# bappr_easyeda_file_source.net
KiCad netlist of a schematic drawn in EasyEDA
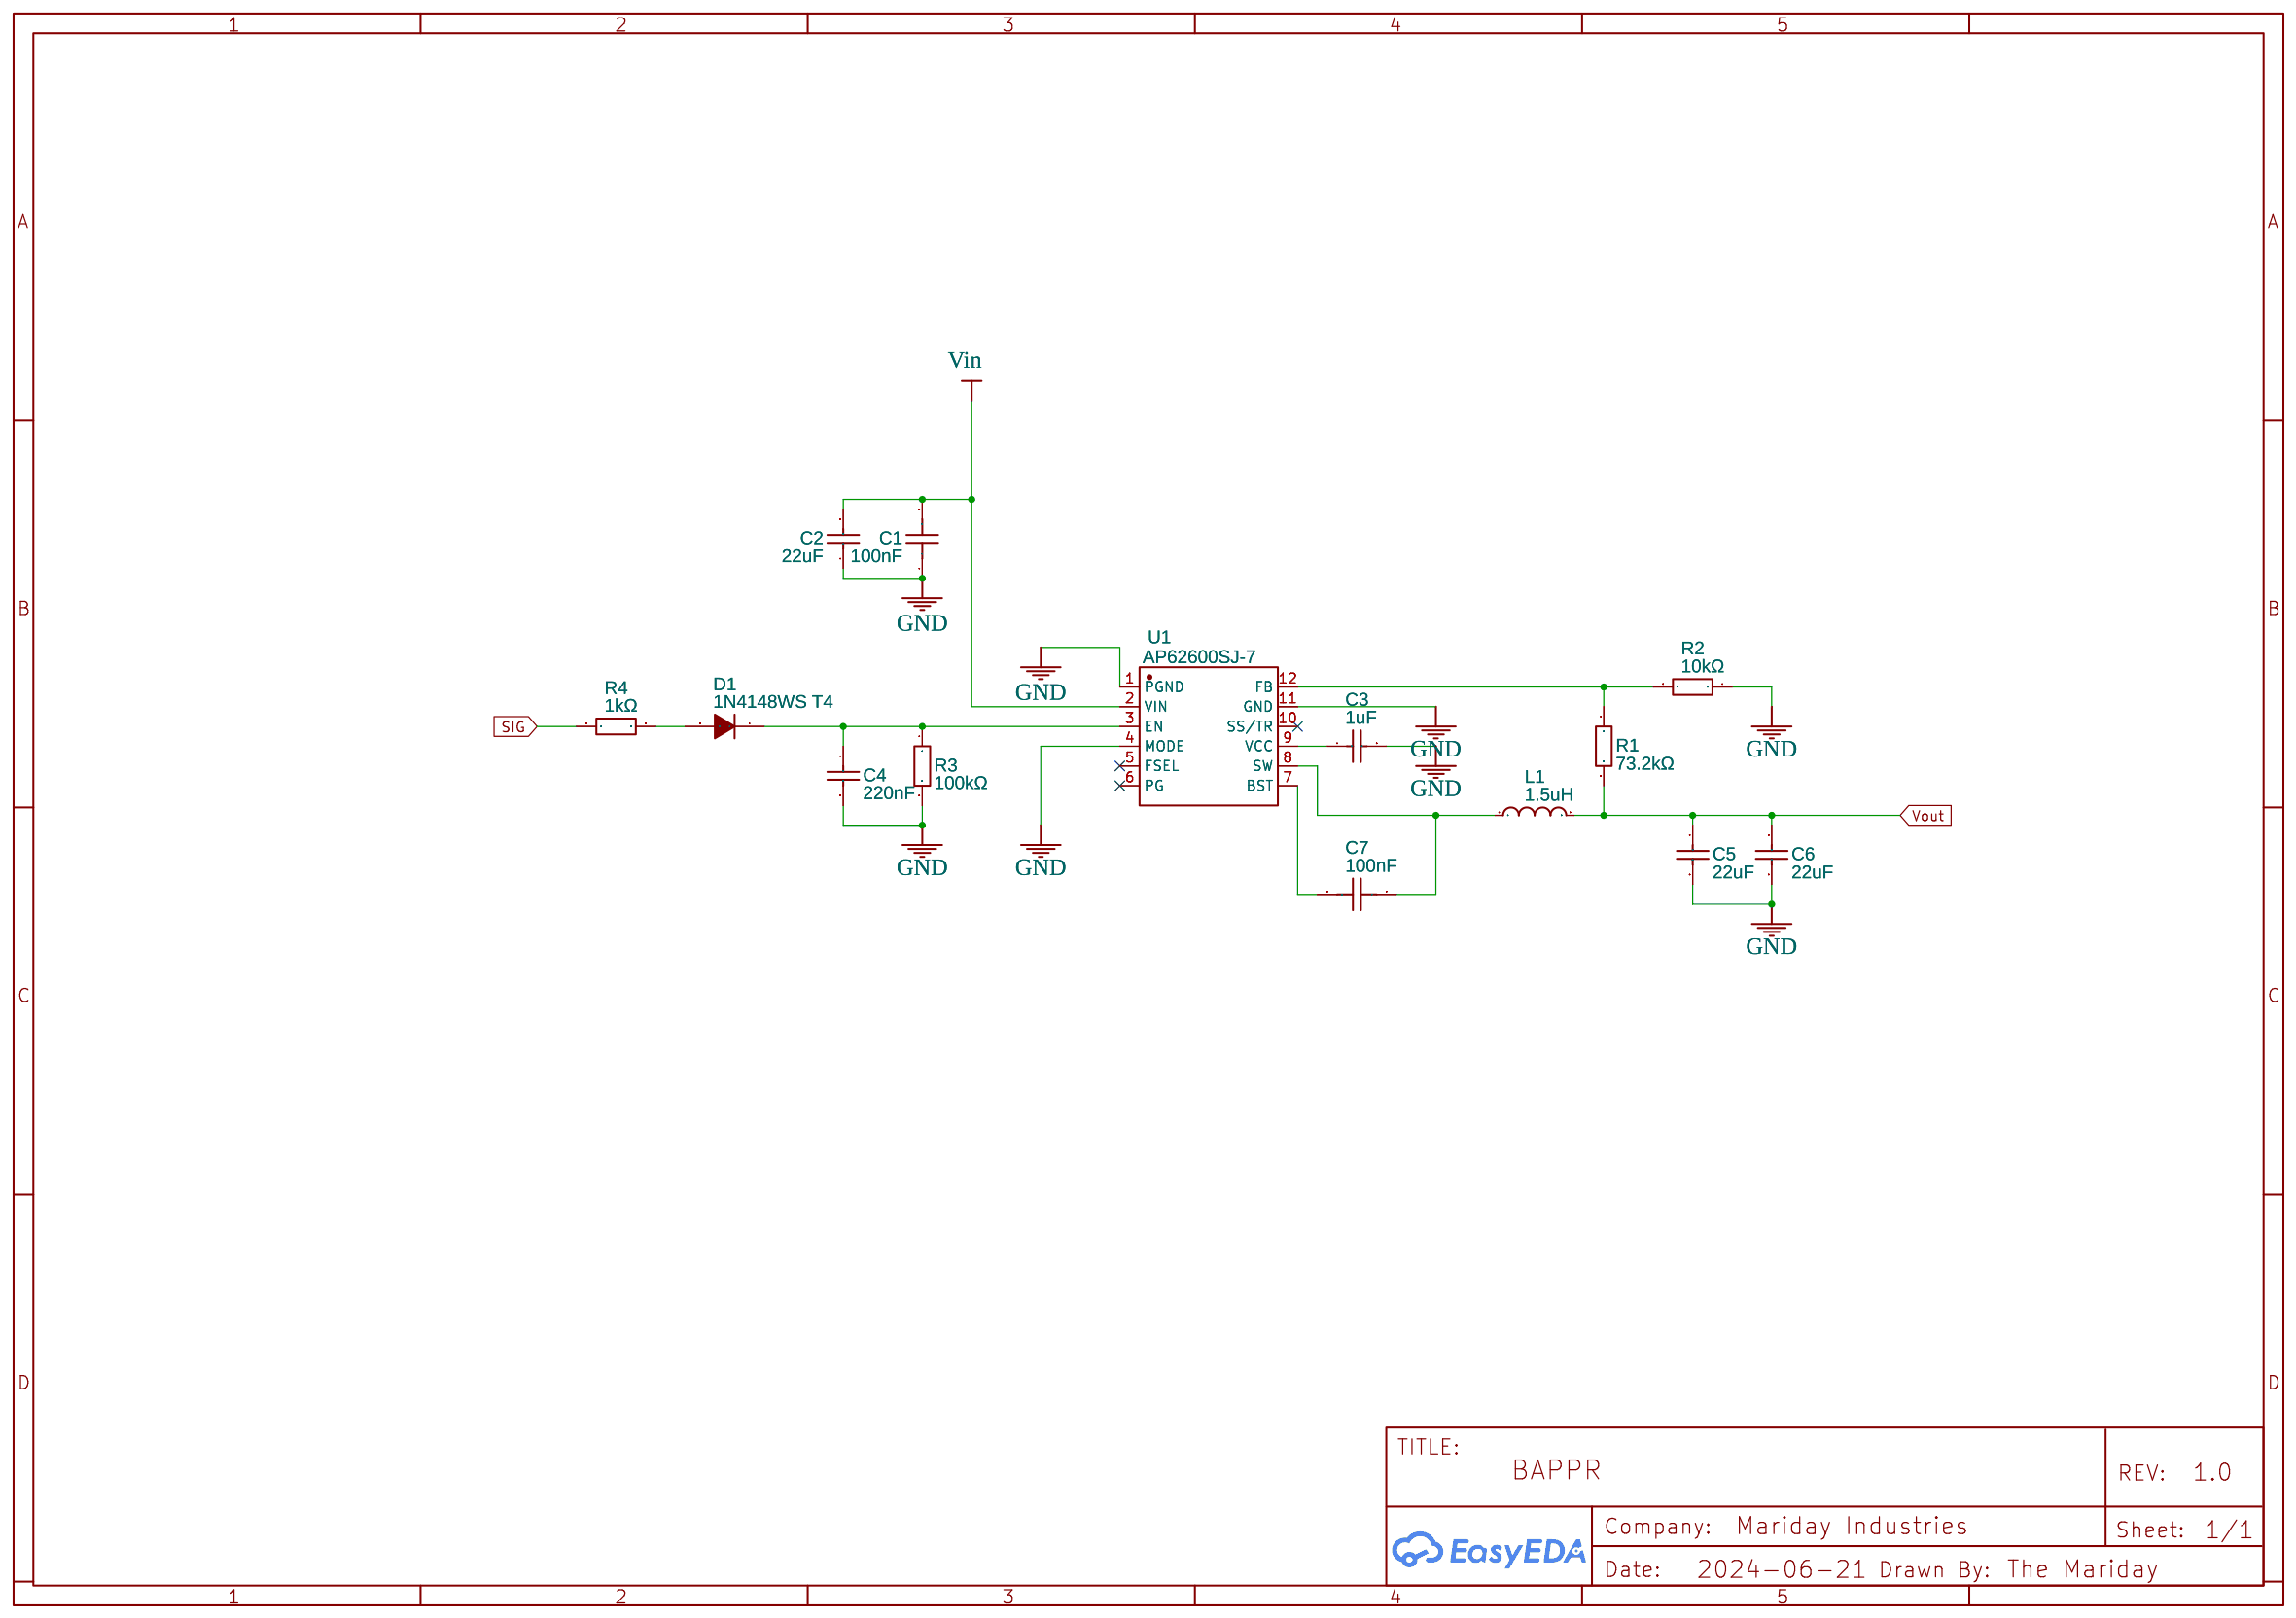
[diagram p0: schematic sheet]

(export (version "E")
  (design (tool "Eeschema 10.0.6"))
  (components
    (comp (ref "C1")
      (value "100nF")
      (fields
        (field (name "Manufacturer Part") "CC0603KRX7R9BB104")
        (field (name "Manufacturer") "YAGEO(国巨)")
      )
      (libsource (lib "") (part "CC0603KRX7R9BB104"))
    )
    (comp (ref "C2")
      (value "22uF")
      (fields
        (field (name "Manufacturer Part") "CL31A226KAHNNNE")
        (field (name "Manufacturer") "SAMSUNG(三星)")
      )
      (libsource (lib "") (part "CL31A226KAHNNNE_1"))
    )
    (comp (ref "C3")
      (value "1uF")
      (fields
        (field (name "Manufacturer Part") "CL10A105KB8NNNC")
        (field (name "Manufacturer") "SAMSUNG(三星)")
      )
      (libsource (lib "") (part "CL10A105KB8NNNC"))
    )
    (comp (ref "C4")
      (value "220nF")
      (fields
        (field (name "Manufacturer Part") "CL10B224KA8NNNC")
        (field (name "Manufacturer") "SAMSUNG(三星)")
      )
      (libsource (lib "") (part "CL10B224KA8NNNC"))
    )
    (comp (ref "C5")
      (value "22uF")
      (fields
        (field (name "Manufacturer Part") "CL31A226KAHNNNE")
        (field (name "Manufacturer") "SAMSUNG(三星)")
      )
      (libsource (lib "") (part "CL31A226KAHNNNE"))
    )
    (comp (ref "C6")
      (value "22uF")
      (fields
        (field (name "Manufacturer Part") "CL31A226KAHNNNE")
        (field (name "Manufacturer") "SAMSUNG(三星)")
      )
      (libsource (lib "") (part "CL31A226KAHNNNE"))
    )
    (comp (ref "C7")
      (value "100nF")
      (fields
        (field (name "Manufacturer Part") "CC0603KRX7R9BB104")
        (field (name "Manufacturer") "YAGEO(国巨)")
      )
      (libsource (lib "") (part "CC0603KRX7R9BB104_1"))
    )
    (comp (ref "D1")
      (value "1N4148WS T4")
      (fields (field (name "Manufacturer Part") "1N4148WS") (field (name "Manufacturer") "CJ(江苏长电/长晶)"))
      (libsource (lib "") (part "1N4148WS T4"))
    )
    (comp (ref "L1")
      (value "1.5uH")
      (fields
        (field (name "Manufacturer Part") "IHLP2525CZER1R5M01")
        (field (name "Manufacturer") "VISHAY(威世)")
      )
      (libsource (lib "") (part "IHLP2525CZER1R5M01"))
    )
    (comp (ref "R1")
      (value "73.2kΩ")
      (fields
        (field (name "Manufacturer Part") "0603WAF7322T5E")
        (field (name "Manufacturer") "UNI-ROYAL(厚声)")
      )
      (libsource (lib "") (part "0603WAF7322T5E"))
    )
    (comp (ref "R2")
      (value "10kΩ")
      (fields
        (field (name "Manufacturer Part") "0603WAF1002T5E")
        (field (name "Manufacturer") "UNI-ROYAL(厚声)")
      )
      (libsource (lib "") (part "0603WAF1002T5E"))
    )
    (comp (ref "R3")
      (value "100kΩ")
      (fields
        (field (name "Manufacturer Part") "0603WAF1003T5E")
        (field (name "Manufacturer") "UNI-ROYAL(厚声)")
      )
      (libsource (lib "") (part "0603WAF1003T5E"))
    )
    (comp (ref "R4")
      (value "1kΩ")
      (fields
        (field (name "Manufacturer Part") "0603WAF1001T5E")
        (field (name "Manufacturer") "UNI-ROYAL(厚声)")
      )
      (libsource (lib "") (part "0603WAF1001T5E"))
    )
    (comp (ref "U1")
      (value "AP62600SJ-7")
      (fields (field (name "Manufacturer") "DIODES(美台)"))
      (libsource (lib "") (part "AP62600SJ-7"))
    )
  )
  (nets
    (net (code "1") (name "GND") (class "Default")
      (node (ref "C1") (pin "1") (pinfunction "1_1") (pintype "unspecified"))
      (node (ref "C2") (pin "1") (pinfunction "1_1") (pintype "input"))
      (node (ref "C3") (pin "2") (pinfunction "2_2") (pintype "input"))
      (node (ref "C4") (pin "2") (pinfunction "2_2") (pintype "input"))
      (node (ref "C5") (pin "2") (pinfunction "2_2") (pintype "input"))
      (node (ref "C6") (pin "2") (pinfunction "2_2") (pintype "input"))
      (node (ref "R2") (pin "1") (pinfunction "1_1") (pintype "input"))
      (node (ref "R3") (pin "2") (pinfunction "2_2") (pintype "input"))
      (node (ref "U1") (pin "1") (pinfunction "PGND_1") (pintype "unspecified"))
      (node (ref "U1") (pin "11") (pinfunction "GND_11") (pintype "unspecified"))
      (node (ref "U1") (pin "4") (pinfunction "MODE_4") (pintype "unspecified"))
    )
    (net (code "2") (name "Net-(D1-A)") (class "Default")
      (node (ref "D1") (pin "2") (pinfunction "A_2") (pintype "unspecified"))
      (node (ref "R4") (pin "2") (pinfunction "2_2") (pintype "input"))
    )
    (net (code "3") (name "Net-(D1-K)") (class "Default")
      (node (ref "C4") (pin "1") (pinfunction "1_1") (pintype "input"))
      (node (ref "D1") (pin "1") (pinfunction "K_1") (pintype "unspecified"))
      (node (ref "R3") (pin "1") (pinfunction "1_1") (pintype "input"))
      (node (ref "U1") (pin "3") (pinfunction "EN_3") (pintype "unspecified"))
    )
    (net (code "4") (name "Net-(U1-BST)") (class "Default")
      (node (ref "C7") (pin "2") (pinfunction "2_2") (pintype "unspecified"))
      (node (ref "U1") (pin "7") (pinfunction "BST_7") (pintype "unspecified"))
    )
    (net (code "5") (name "Net-(U1-FB)") (class "Default")
      (node (ref "R1") (pin "1") (pinfunction "1_1") (pintype "input"))
      (node (ref "R2") (pin "2") (pinfunction "2_2") (pintype "input"))
      (node (ref "U1") (pin "12") (pinfunction "FB_12") (pintype "unspecified"))
    )
    (net (code "6") (name "Net-(U1-SW)") (class "Default")
      (node (ref "C7") (pin "1") (pinfunction "1_1") (pintype "unspecified"))
      (node (ref "L1") (pin "1") (pinfunction "1_1") (pintype "unspecified"))
      (node (ref "U1") (pin "8") (pinfunction "SW_8") (pintype "unspecified"))
    )
    (net (code "7") (name "Net-(U1-VCC)") (class "Default")
      (node (ref "C3") (pin "1") (pinfunction "1_1") (pintype "input"))
      (node (ref "U1") (pin "9") (pinfunction "VCC_9") (pintype "unspecified"))
    )
    (net (code "8") (name "SIG") (class "Default")
      (node (ref "R4") (pin "1") (pinfunction "1_1") (pintype "input"))
    )
    (net (code "9") (name "Vin") (class "Default")
      (node (ref "C1") (pin "2") (pinfunction "2_2") (pintype "unspecified"))
      (node (ref "C2") (pin "2") (pinfunction "2_2") (pintype "input"))
      (node (ref "U1") (pin "2") (pinfunction "VIN_2") (pintype "unspecified"))
    )
    (net (code "10") (name "Vout") (class "Default")
      (node (ref "C5") (pin "1") (pinfunction "1_1") (pintype "input"))
      (node (ref "C6") (pin "1") (pinfunction "1_1") (pintype "input"))
      (node (ref "L1") (pin "2") (pinfunction "2_2") (pintype "unspecified"))
      (node (ref "R1") (pin "2") (pinfunction "2_2") (pintype "input"))
    )
    (net (code "11") (name "unconnected-(U1-FSEL-Pad5)") (class "Default")
      (node (ref "U1") (pin "5") (pinfunction "FSEL_5") (pintype "unspecified+no_connect"))
    )
    (net (code "12") (name "unconnected-(U1-PG-Pad6)") (class "Default")
      (node (ref "U1") (pin "6") (pinfunction "PG_6") (pintype "unspecified+no_connect"))
    )
    (net (code "13") (name "unconnected-(U1-SS{slash}TR-Pad10)") (class "Default")
      (node (ref "U1") (pin "10") (pinfunction "SS/TR_10") (pintype "unspecified+no_connect"))
    )
  )
)
